# destilador_pcb.net
KiCad netlist of a schematic drawn in EAGLE
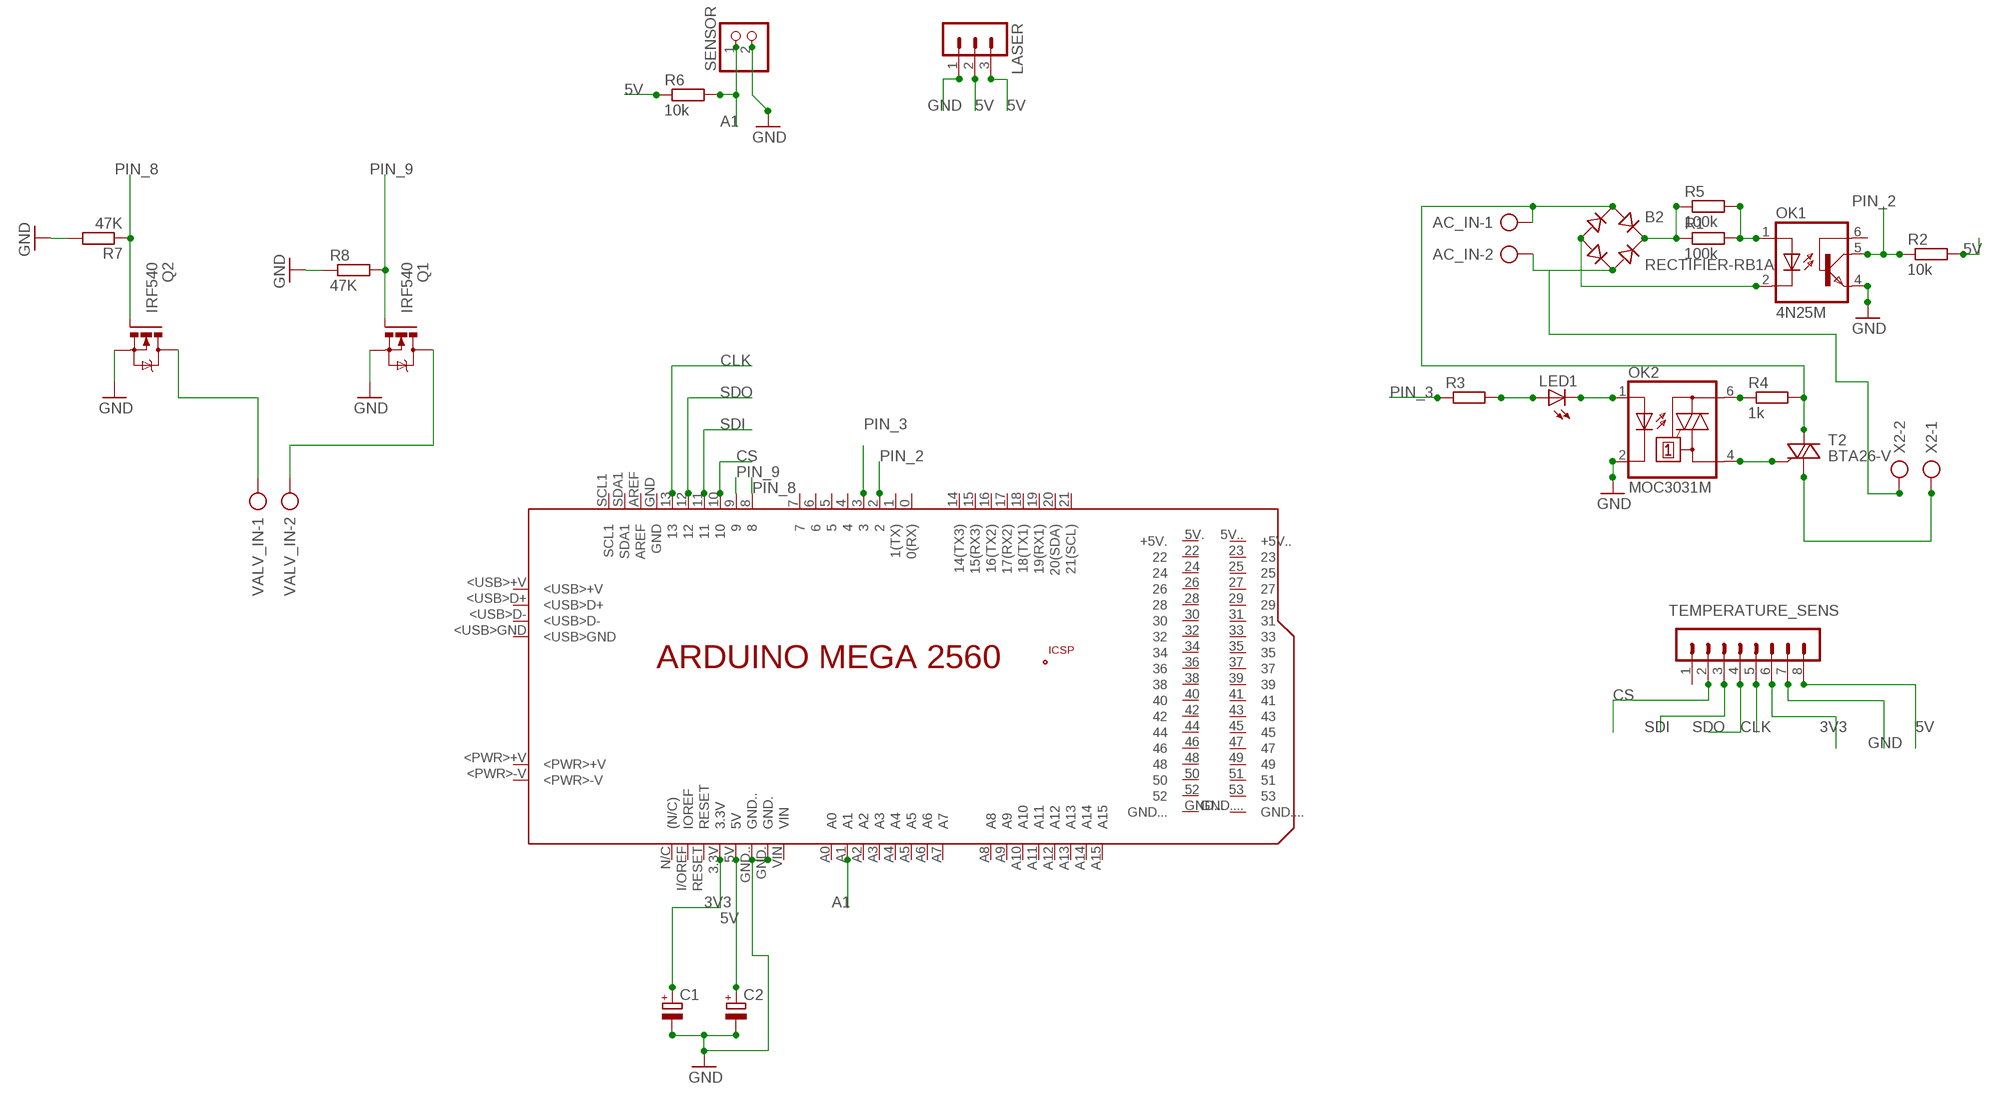
[diagram p0: schematic, sheet 1]

(export (version "E")
  (design (tool "Eeschema 10.0.6"))
  (components
    (comp (ref "AC_IN")
      (value "AK300/2")
      (footprint "eagle-import:AK300_2")
      (libsource (lib "eagle-import") (part "AK300/2"))
    )
    (comp (ref "B2")
      (value "RECTIFIER-RB1A")
      (footprint "eagle-import:RB1A")
      (libsource (lib "eagle-import") (part "RECTIFIER-RB1A"))
    )
    (comp (ref "C1")
      (value "CPOL-EUE2,5-6E")
      (footprint "eagle-import:E2,5-6E")
      (libsource (lib "eagle-import") (part "CPOL-EUE2,5-6E"))
    )
    (comp (ref "C2")
      (value "CPOL-EUE2,5-6E")
      (footprint "eagle-import:E2,5-6E")
      (libsource (lib "eagle-import") (part "CPOL-EUE2,5-6E"))
    )
    (comp (ref "LASER")
      (value "MA03-1")
      (footprint "eagle-import:MA03-1")
      (libsource (lib "eagle-import") (part "MA03-1"))
    )
    (comp (ref "LED1")
      (value "LED5MM")
      (footprint "eagle-import:LED5MM")
      (libsource (lib "eagle-import") (part "LED5MM"))
    )
    (comp (ref "OK1")
      (value "4N25M")
      (footprint "eagle-import:DIL06")
      (fields (field (name "MPN") "4N25-M"))
      (libsource (lib "eagle-import") (part "4N?M25"))
    )
    (comp (ref "OK2")
      (value "MOC3031M")
      (footprint "eagle-import:DIL06")
      (fields (field (name "MF") "FAIRCHILD SEMICONDUCTOR"))
      (libsource (lib "eagle-import") (part "MOC3031M"))
    )
    (comp (ref "PCB1")
      (value "ARDUINO_MEGA2560")
      (footprint "eagle-import:ARDUINO_MEGA2560")
      (libsource (lib "eagle-import") (part "ARDUINO_MEGA2560"))
    )
    (comp (ref "Q1")
      (value "IRF540")
      (footprint "eagle-import:TO220BV")
      (libsource (lib "eagle-import") (part "IRF540"))
    )
    (comp (ref "Q2")
      (value "IRF540")
      (footprint "eagle-import:TO220BV")
      (libsource (lib "eagle-import") (part "IRF540"))
    )
    (comp (ref "R1")
      (value "100k")
      (footprint "eagle-import:0207_7")
      (libsource (lib "eagle-import") (part "R-EU_0207/7"))
    )
    (comp (ref "R2")
      (value "10k")
      (footprint "eagle-import:0207_7")
      (libsource (lib "eagle-import") (part "R-EU_0207/7"))
    )
    (comp (ref "R3")
      (value "R-EU_0207/7")
      (footprint "eagle-import:0207_7")
      (libsource (lib "eagle-import") (part "R-EU_0207/7"))
    )
    (comp (ref "R4")
      (value "1k")
      (footprint "eagle-import:0207_7")
      (libsource (lib "eagle-import") (part "R-EU_0207/7"))
    )
    (comp (ref "R5")
      (value "100k")
      (footprint "eagle-import:0207_7")
      (libsource (lib "eagle-import") (part "R-EU_0207/7"))
    )
    (comp (ref "R6")
      (value "10k")
      (footprint "eagle-import:0207_7")
      (libsource (lib "eagle-import") (part "R-EU_0207/7"))
    )
    (comp (ref "R7")
      (value "47K")
      (footprint "eagle-import:0207_7")
      (libsource (lib "eagle-import") (part "R-EU_0207/7"))
    )
    (comp (ref "R8")
      (value "47K")
      (footprint "eagle-import:0207_7")
      (libsource (lib "eagle-import") (part "R-EU_0207/7"))
    )
    (comp (ref "SENSOR")
      (value "PINHD-1X2")
      (footprint "eagle-import:1X02")
      (libsource (lib "eagle-import") (part "PINHD-1X2"))
    )
    (comp (ref "T2")
      (value "BTA26-V")
      (footprint "eagle-import:TOP3S-1")
      (libsource (lib "eagle-import") (part "BTA26-V"))
    )
    (comp (ref "TEMPERATURE_SENS")
      (value "MA08-1")
      (footprint "eagle-import:MA08-1")
      (libsource (lib "eagle-import") (part "MA08-1"))
    )
    (comp (ref "VALV_IN")
      (value "AK500/2-H")
      (footprint "eagle-import:AK500_2-H")
      (libsource (lib "eagle-import") (part "AK500/2-H"))
    )
    (comp (ref "X2")
      (value "AK300/2")
      (footprint "eagle-import:AK300_2")
      (libsource (lib "eagle-import") (part "AK300/2"))
    )
  )
  (nets
    (net (code "1") (name "/3V3") (class "Default")
      (node (ref "C1") (pin "+") (pinfunction "+_+") (pintype "passive"))
      (node (ref "PCB1") (pin "3.3V") (pinfunction "3.3V_3.3V") (pintype "bidirectional"))
      (node (ref "TEMPERATURE_SENS") (pin "6") (pinfunction "6_6") (pintype "passive"))
    )
    (net (code "2") (name "/5V") (class "Default")
      (node (ref "C2") (pin "+") (pinfunction "+_+") (pintype "passive"))
      (node (ref "LASER") (pin "2") (pinfunction "2_2") (pintype "passive"))
      (node (ref "LASER") (pin "3") (pinfunction "3_3") (pintype "passive"))
      (node (ref "PCB1") (pin "5V") (pinfunction "5V_5V") (pintype "bidirectional"))
      (node (ref "R2") (pin "2") (pinfunction "2_2") (pintype "passive"))
      (node (ref "R6") (pin "1") (pinfunction "1_1") (pintype "passive"))
      (node (ref "TEMPERATURE_SENS") (pin "8") (pinfunction "8_8") (pintype "passive"))
    )
    (net (code "3") (name "/A1") (class "Default")
      (node (ref "PCB1") (pin "A1") (pinfunction "A1_A1") (pintype "bidirectional"))
      (node (ref "R6") (pin "2") (pinfunction "2_2") (pintype "passive"))
      (node (ref "SENSOR") (pin "1") (pinfunction "1_1") (pintype "passive"))
    )
    (net (code "4") (name "/CLK") (class "Default")
      (node (ref "PCB1") (pin "13") (pinfunction "13_13") (pintype "bidirectional"))
      (node (ref "TEMPERATURE_SENS") (pin "5") (pinfunction "5_5") (pintype "passive"))
    )
    (net (code "5") (name "/CS") (class "Default")
      (node (ref "PCB1") (pin "10") (pinfunction "10_10") (pintype "bidirectional"))
      (node (ref "TEMPERATURE_SENS") (pin "2") (pinfunction "2_2") (pintype "passive"))
    )
    (net (code "6") (name "/PIN_2") (class "Default")
      (node (ref "OK1") (pin "5") (pinfunction "COL_5") (pintype "passive"))
      (node (ref "PCB1") (pin "2") (pinfunction "2_2") (pintype "bidirectional"))
      (node (ref "R2") (pin "1") (pinfunction "1_1") (pintype "passive"))
    )
    (net (code "7") (name "/PIN_3") (class "Default")
      (node (ref "PCB1") (pin "3") (pinfunction "3_3") (pintype "bidirectional"))
      (node (ref "R3") (pin "1") (pinfunction "1_1") (pintype "passive"))
    )
    (net (code "8") (name "/PIN_8") (class "Default")
      (node (ref "PCB1") (pin "8") (pinfunction "8_8") (pintype "bidirectional"))
      (node (ref "Q2") (pin "G") (pinfunction "G_G") (pintype "passive"))
      (node (ref "R7") (pin "1") (pinfunction "1_1") (pintype "passive"))
    )
    (net (code "9") (name "/PIN_9") (class "Default")
      (node (ref "PCB1") (pin "9") (pinfunction "9_9") (pintype "bidirectional"))
      (node (ref "Q1") (pin "G") (pinfunction "G_G") (pintype "passive"))
      (node (ref "R8") (pin "2") (pinfunction "2_2") (pintype "passive"))
    )
    (net (code "10") (name "/SDI") (class "Default")
      (node (ref "PCB1") (pin "11") (pinfunction "11_11") (pintype "bidirectional"))
      (node (ref "TEMPERATURE_SENS") (pin "3") (pinfunction "3_3") (pintype "passive"))
    )
    (net (code "11") (name "/SDO") (class "Default")
      (node (ref "PCB1") (pin "12") (pinfunction "12_12") (pintype "bidirectional"))
      (node (ref "TEMPERATURE_SENS") (pin "4") (pinfunction "4_4") (pintype "passive"))
    )
    (net (code "12") (name "GND") (class "Default")
      (node (ref "C1") (pin "-") (pinfunction "-_-") (pintype "passive"))
      (node (ref "C2") (pin "-") (pinfunction "-_-") (pintype "passive"))
      (node (ref "LASER") (pin "1") (pinfunction "1_1") (pintype "passive"))
      (node (ref "OK1") (pin "4") (pinfunction "EMI_4") (pintype "passive"))
      (node (ref "OK2") (pin "2") (pinfunction "C_2") (pintype "passive"))
      (node (ref "PCB1") (pin "GND.") (pinfunction "GND._GND.") (pintype "bidirectional"))
      (node (ref "PCB1") (pin "GND..") (pinfunction "GND.._GND..") (pintype "bidirectional"))
      (node (ref "Q1") (pin "S") (pinfunction "S_S") (pintype "passive"))
      (node (ref "Q2") (pin "S") (pinfunction "S_S") (pintype "passive"))
      (node (ref "R7") (pin "2") (pinfunction "2_2") (pintype "passive"))
      (node (ref "R8") (pin "1") (pinfunction "1_1") (pintype "passive"))
      (node (ref "SENSOR") (pin "2") (pinfunction "2_2") (pintype "passive"))
      (node (ref "TEMPERATURE_SENS") (pin "7") (pinfunction "7_7") (pintype "passive"))
    )
    (net (code "13") (name "Net-(AC_INA-KL)") (class "Default")
      (node (ref "AC_IN") (pin "1") (pinfunction "KL_1") (pintype "passive"))
      (node (ref "B2") (pin "AC1") (pinfunction "AC1_AC1") (pintype "passive"))
      (node (ref "R4") (pin "2") (pinfunction "2_2") (pintype "passive"))
      (node (ref "T2") (pin "A2") (pinfunction "A2_A2") (pintype "passive"))
    )
    (net (code "14") (name "Net-(AC_INB-KL)") (class "Default")
      (node (ref "AC_IN") (pin "2") (pinfunction "KL_2") (pintype "passive"))
      (node (ref "B2") (pin "AC2") (pinfunction "AC2_AC2") (pintype "passive"))
      (node (ref "X2") (pin "2") (pinfunction "KL_2") (pintype "passive"))
    )
    (net (code "15") (name "Net-(B2-Pad+)") (class "Default")
      (node (ref "B2") (pin "+") (pinfunction "+_+") (pintype "passive"))
      (node (ref "R1") (pin "1") (pinfunction "1_1") (pintype "passive"))
      (node (ref "R5") (pin "1") (pinfunction "1_1") (pintype "passive"))
    )
    (net (code "16") (name "Net-(LED1-C)") (class "Default")
      (node (ref "LED1") (pin "K") (pinfunction "C_K") (pintype "passive"))
      (node (ref "OK2") (pin "1") (pinfunction "A_1") (pintype "passive"))
    )
    (net (code "17") (name "Net-(LED1-PadA)") (class "Default")
      (node (ref "LED1") (pin "A") (pinfunction "A_A") (pintype "passive"))
      (node (ref "R3") (pin "2") (pinfunction "2_2") (pintype "passive"))
    )
    (net (code "18") (name "Net-(OK1-A)") (class "Default")
      (node (ref "OK1") (pin "1") (pinfunction "A_1") (pintype "passive"))
      (node (ref "R1") (pin "2") (pinfunction "2_2") (pintype "passive"))
      (node (ref "R5") (pin "2") (pinfunction "2_2") (pintype "passive"))
    )
    (net (code "19") (name "Net-(OK1-C)") (class "Default")
      (node (ref "B2") (pin "-") (pinfunction "-_-") (pintype "passive"))
      (node (ref "OK1") (pin "2") (pinfunction "C_2") (pintype "passive"))
    )
    (net (code "20") (name "Net-(OK2-A1)") (class "Default")
      (node (ref "OK2") (pin "4") (pinfunction "A1_4") (pintype "passive"))
      (node (ref "T2") (pin "G") (pinfunction "G_G") (pintype "passive"))
    )
    (net (code "21") (name "Net-(OK2-A2)") (class "Default")
      (node (ref "OK2") (pin "6") (pinfunction "A2_6") (pintype "passive"))
      (node (ref "R4") (pin "1") (pinfunction "1_1") (pintype "passive"))
    )
    (net (code "22") (name "Net-(VALV_INA-KL)") (class "Default")
      (node (ref "Q2") (pin "D") (pinfunction "D_D") (pintype "passive"))
      (node (ref "VALV_IN") (pin "1") (pinfunction "KL_1") (pintype "passive"))
    )
    (net (code "23") (name "Net-(VALV_INB-KL)") (class "Default")
      (node (ref "Q1") (pin "D") (pinfunction "D_D") (pintype "passive"))
      (node (ref "VALV_IN") (pin "2") (pinfunction "KL_2") (pintype "passive"))
    )
    (net (code "24") (name "Net-(X2A-KL)") (class "Default")
      (node (ref "T2") (pin "A1") (pinfunction "A1_A1") (pintype "passive"))
      (node (ref "X2") (pin "1") (pinfunction "KL_1") (pintype "passive"))
    )
    (net (code "25") (name "unconnected-(OK1-BAS-Pad6)") (class "Default")
      (node (ref "OK1") (pin "6") (pinfunction "BAS_6") (pintype "passive"))
    )
    (net (code "26") (name "unconnected-(PCB1-(N{slash}C)-PadN{slash}C)") (class "Default")
      (node (ref "PCB1") (pin "N/C") (pinfunction "(N/C)_N/C") (pintype "bidirectional"))
    )
    (net (code "27") (name "unconnected-(PCB1-+5V.-Pad5V.)") (class "Default")
      (node (ref "PCB1") (pin "5V.") (pinfunction "+5V._5V.") (pintype "bidirectional"))
    )
    (net (code "28") (name "unconnected-(PCB1-+5V..-Pad5V..)") (class "Default")
      (node (ref "PCB1") (pin "5V..") (pinfunction "+5V.._5V..") (pintype "bidirectional"))
    )
    (net (code "29") (name "unconnected-(PCB1-0(RX)-Pad0)") (class "Default")
      (node (ref "PCB1") (pin "0") (pinfunction "0(RX)_0") (pintype "bidirectional"))
    )
    (net (code "30") (name "unconnected-(PCB1-1(TX)-Pad1)") (class "Default")
      (node (ref "PCB1") (pin "1") (pinfunction "1(TX)_1") (pintype "bidirectional"))
    )
    (net (code "31") (name "unconnected-(PCB1-14(TX3)-Pad14)") (class "Default")
      (node (ref "PCB1") (pin "14") (pinfunction "14(TX3)_14") (pintype "bidirectional"))
    )
    (net (code "32") (name "unconnected-(PCB1-15(RX3)-Pad15)") (class "Default")
      (node (ref "PCB1") (pin "15") (pinfunction "15(RX3)_15") (pintype "bidirectional"))
    )
    (net (code "33") (name "unconnected-(PCB1-16(TX2)-Pad16)") (class "Default")
      (node (ref "PCB1") (pin "16") (pinfunction "16(TX2)_16") (pintype "bidirectional"))
    )
    (net (code "34") (name "unconnected-(PCB1-17(RX2)-Pad17)") (class "Default")
      (node (ref "PCB1") (pin "17") (pinfunction "17(RX2)_17") (pintype "bidirectional"))
    )
    (net (code "35") (name "unconnected-(PCB1-18(TX1)-Pad18)") (class "Default")
      (node (ref "PCB1") (pin "18") (pinfunction "18(TX1)_18") (pintype "bidirectional"))
    )
    (net (code "36") (name "unconnected-(PCB1-19(RX1)-Pad19)") (class "Default")
      (node (ref "PCB1") (pin "19") (pinfunction "19(RX1)_19") (pintype "bidirectional"))
    )
    (net (code "37") (name "unconnected-(PCB1-20(SDA)-Pad20)") (class "Default")
      (node (ref "PCB1") (pin "20") (pinfunction "20(SDA)_20") (pintype "bidirectional"))
    )
    (net (code "38") (name "unconnected-(PCB1-21(SCL)-Pad21)") (class "Default")
      (node (ref "PCB1") (pin "21") (pinfunction "21(SCL)_21") (pintype "bidirectional"))
    )
    (net (code "39") (name "unconnected-(PCB1-IOREF-PadI{slash}OREF)") (class "Default")
      (node (ref "PCB1") (pin "I/OREF") (pinfunction "IOREF_I/OREF") (pintype "bidirectional"))
    )
    (net (code "40") (name "unconnected-(PCB1-Pad+5V_)") (class "Default")
      (node (ref "PCB1") (pin "+5V_") (pinfunction "+5V__+5V_") (pintype "bidirectional"))
    )
    (net (code "41") (name "unconnected-(PCB1-Pad4)") (class "Default")
      (node (ref "PCB1") (pin "4") (pinfunction "4_4") (pintype "bidirectional"))
    )
    (net (code "42") (name "unconnected-(PCB1-Pad5)") (class "Default")
      (node (ref "PCB1") (pin "5") (pinfunction "5_5") (pintype "bidirectional"))
    )
    (net (code "43") (name "unconnected-(PCB1-Pad6)") (class "Default")
      (node (ref "PCB1") (pin "6") (pinfunction "6_6") (pintype "bidirectional"))
    )
    (net (code "44") (name "unconnected-(PCB1-Pad7)") (class "Default")
      (node (ref "PCB1") (pin "7") (pinfunction "7_7") (pintype "bidirectional"))
    )
    (net (code "45") (name "unconnected-(PCB1-Pad22)") (class "Default")
      (node (ref "PCB1") (pin "22") (pinfunction "22_22") (pintype "bidirectional"))
    )
    (net (code "46") (name "unconnected-(PCB1-Pad23)") (class "Default")
      (node (ref "PCB1") (pin "23") (pinfunction "23_23") (pintype "bidirectional"))
    )
    (net (code "47") (name "unconnected-(PCB1-Pad24)") (class "Default")
      (node (ref "PCB1") (pin "24") (pinfunction "24_24") (pintype "bidirectional"))
    )
    (net (code "48") (name "unconnected-(PCB1-Pad25)") (class "Default")
      (node (ref "PCB1") (pin "25") (pinfunction "25_25") (pintype "bidirectional"))
    )
    (net (code "49") (name "unconnected-(PCB1-Pad26)") (class "Default")
      (node (ref "PCB1") (pin "26") (pinfunction "26_26") (pintype "bidirectional"))
    )
    (net (code "50") (name "unconnected-(PCB1-Pad27)") (class "Default")
      (node (ref "PCB1") (pin "27") (pinfunction "27_27") (pintype "bidirectional"))
    )
    (net (code "51") (name "unconnected-(PCB1-Pad28)") (class "Default")
      (node (ref "PCB1") (pin "28") (pinfunction "28_28") (pintype "bidirectional"))
    )
    (net (code "52") (name "unconnected-(PCB1-Pad29)") (class "Default")
      (node (ref "PCB1") (pin "29") (pinfunction "29_29") (pintype "bidirectional"))
    )
    (net (code "53") (name "unconnected-(PCB1-Pad30)") (class "Default")
      (node (ref "PCB1") (pin "30") (pinfunction "30_30") (pintype "bidirectional"))
    )
    (net (code "54") (name "unconnected-(PCB1-Pad31)") (class "Default")
      (node (ref "PCB1") (pin "31") (pinfunction "31_31") (pintype "bidirectional"))
    )
    (net (code "55") (name "unconnected-(PCB1-Pad32)") (class "Default")
      (node (ref "PCB1") (pin "32") (pinfunction "32_32") (pintype "bidirectional"))
    )
    (net (code "56") (name "unconnected-(PCB1-Pad33)") (class "Default")
      (node (ref "PCB1") (pin "33") (pinfunction "33_33") (pintype "bidirectional"))
    )
    (net (code "57") (name "unconnected-(PCB1-Pad34)") (class "Default")
      (node (ref "PCB1") (pin "34") (pinfunction "34_34") (pintype "bidirectional"))
    )
    (net (code "58") (name "unconnected-(PCB1-Pad35)") (class "Default")
      (node (ref "PCB1") (pin "35") (pinfunction "35_35") (pintype "bidirectional"))
    )
    (net (code "59") (name "unconnected-(PCB1-Pad36)") (class "Default")
      (node (ref "PCB1") (pin "36") (pinfunction "36_36") (pintype "bidirectional"))
    )
    (net (code "60") (name "unconnected-(PCB1-Pad37)") (class "Default")
      (node (ref "PCB1") (pin "37") (pinfunction "37_37") (pintype "bidirectional"))
    )
    (net (code "61") (name "unconnected-(PCB1-Pad38)") (class "Default")
      (node (ref "PCB1") (pin "38") (pinfunction "38_38") (pintype "bidirectional"))
    )
    (net (code "62") (name "unconnected-(PCB1-Pad39)") (class "Default")
      (node (ref "PCB1") (pin "39") (pinfunction "39_39") (pintype "bidirectional"))
    )
    (net (code "63") (name "unconnected-(PCB1-Pad40)") (class "Default")
      (node (ref "PCB1") (pin "40") (pinfunction "40_40") (pintype "bidirectional"))
    )
    (net (code "64") (name "unconnected-(PCB1-Pad41)") (class "Default")
      (node (ref "PCB1") (pin "41") (pinfunction "41_41") (pintype "bidirectional"))
    )
    (net (code "65") (name "unconnected-(PCB1-Pad42)") (class "Default")
      (node (ref "PCB1") (pin "42") (pinfunction "42_42") (pintype "bidirectional"))
    )
    (net (code "66") (name "unconnected-(PCB1-Pad43)") (class "Default")
      (node (ref "PCB1") (pin "43") (pinfunction "43_43") (pintype "bidirectional"))
    )
    (net (code "67") (name "unconnected-(PCB1-Pad44)") (class "Default")
      (node (ref "PCB1") (pin "44") (pinfunction "44_44") (pintype "bidirectional"))
    )
    (net (code "68") (name "unconnected-(PCB1-Pad45)") (class "Default")
      (node (ref "PCB1") (pin "45") (pinfunction "45_45") (pintype "bidirectional"))
    )
    (net (code "69") (name "unconnected-(PCB1-Pad46)") (class "Default")
      (node (ref "PCB1") (pin "46") (pinfunction "46_46") (pintype "bidirectional"))
    )
    (net (code "70") (name "unconnected-(PCB1-Pad47)") (class "Default")
      (node (ref "PCB1") (pin "47") (pinfunction "47_47") (pintype "bidirectional"))
    )
    (net (code "71") (name "unconnected-(PCB1-Pad48)") (class "Default")
      (node (ref "PCB1") (pin "48") (pinfunction "48_48") (pintype "bidirectional"))
    )
    (net (code "72") (name "unconnected-(PCB1-Pad49)") (class "Default")
      (node (ref "PCB1") (pin "49") (pinfunction "49_49") (pintype "bidirectional"))
    )
    (net (code "73") (name "unconnected-(PCB1-Pad50)") (class "Default")
      (node (ref "PCB1") (pin "50") (pinfunction "50_50") (pintype "bidirectional"))
    )
    (net (code "74") (name "unconnected-(PCB1-Pad51)") (class "Default")
      (node (ref "PCB1") (pin "51") (pinfunction "51_51") (pintype "bidirectional"))
    )
    (net (code "75") (name "unconnected-(PCB1-Pad52)") (class "Default")
      (node (ref "PCB1") (pin "52") (pinfunction "52_52") (pintype "bidirectional"))
    )
    (net (code "76") (name "unconnected-(PCB1-Pad53)") (class "Default")
      (node (ref "PCB1") (pin "53") (pinfunction "53_53") (pintype "bidirectional"))
    )
    (net (code "77") (name "unconnected-(PCB1-Pad<PWR>+V)") (class "Default")
      (node (ref "PCB1") (pin "<PWR>+V") (pinfunction "<PWR>+V_<PWR>+V") (pintype "no_connect"))
    )
    (net (code "78") (name "unconnected-(PCB1-Pad<PWR>-V)") (class "Default")
      (node (ref "PCB1") (pin "<PWR>-V") (pinfunction "<PWR>-V_<PWR>-V") (pintype "no_connect"))
    )
    (net (code "79") (name "unconnected-(PCB1-Pad<USB>+V)") (class "Default")
      (node (ref "PCB1") (pin "<USB>+V") (pinfunction "<USB>+V_<USB>+V") (pintype "no_connect"))
    )
    (net (code "80") (name "unconnected-(PCB1-Pad<USB>D+)") (class "Default")
      (node (ref "PCB1") (pin "<USB>D+") (pinfunction "<USB>D+_<USB>D+") (pintype "no_connect"))
    )
    (net (code "81") (name "unconnected-(PCB1-Pad<USB>D-)") (class "Default")
      (node (ref "PCB1") (pin "<USB>D-") (pinfunction "<USB>D-_<USB>D-") (pintype "no_connect"))
    )
    (net (code "82") (name "unconnected-(PCB1-Pad<USB>GND)") (class "Default")
      (node (ref "PCB1") (pin "<USB>GND") (pinfunction "<USB>GND_<USB>GND") (pintype "no_connect"))
    )
    (net (code "83") (name "unconnected-(PCB1-PadA0)") (class "Default")
      (node (ref "PCB1") (pin "A0") (pinfunction "A0_A0") (pintype "bidirectional"))
    )
    (net (code "84") (name "unconnected-(PCB1-PadA2)") (class "Default")
      (node (ref "PCB1") (pin "A2") (pinfunction "A2_A2") (pintype "bidirectional"))
    )
    (net (code "85") (name "unconnected-(PCB1-PadA3)") (class "Default")
      (node (ref "PCB1") (pin "A3") (pinfunction "A3_A3") (pintype "bidirectional"))
    )
    (net (code "86") (name "unconnected-(PCB1-PadA4)") (class "Default")
      (node (ref "PCB1") (pin "A4") (pinfunction "A4_A4") (pintype "bidirectional"))
    )
    (net (code "87") (name "unconnected-(PCB1-PadA5)") (class "Default")
      (node (ref "PCB1") (pin "A5") (pinfunction "A5_A5") (pintype "bidirectional"))
    )
    (net (code "88") (name "unconnected-(PCB1-PadA6)") (class "Default")
      (node (ref "PCB1") (pin "A6") (pinfunction "A6_A6") (pintype "bidirectional"))
    )
    (net (code "89") (name "unconnected-(PCB1-PadA7)") (class "Default")
      (node (ref "PCB1") (pin "A7") (pinfunction "A7_A7") (pintype "bidirectional"))
    )
    (net (code "90") (name "unconnected-(PCB1-PadA8)") (class "Default")
      (node (ref "PCB1") (pin "A8") (pinfunction "A8_A8") (pintype "bidirectional"))
    )
    (net (code "91") (name "unconnected-(PCB1-PadA9)") (class "Default")
      (node (ref "PCB1") (pin "A9") (pinfunction "A9_A9") (pintype "bidirectional"))
    )
    (net (code "92") (name "unconnected-(PCB1-PadA10)") (class "Default")
      (node (ref "PCB1") (pin "A10") (pinfunction "A10_A10") (pintype "bidirectional"))
    )
    (net (code "93") (name "unconnected-(PCB1-PadA11)") (class "Default")
      (node (ref "PCB1") (pin "A11") (pinfunction "A11_A11") (pintype "bidirectional"))
    )
    (net (code "94") (name "unconnected-(PCB1-PadA12)") (class "Default")
      (node (ref "PCB1") (pin "A12") (pinfunction "A12_A12") (pintype "bidirectional"))
    )
    (net (code "95") (name "unconnected-(PCB1-PadA13)") (class "Default")
      (node (ref "PCB1") (pin "A13") (pinfunction "A13_A13") (pintype "bidirectional"))
    )
    (net (code "96") (name "unconnected-(PCB1-PadA14)") (class "Default")
      (node (ref "PCB1") (pin "A14") (pinfunction "A14_A14") (pintype "bidirectional"))
    )
    (net (code "97") (name "unconnected-(PCB1-PadA15)") (class "Default")
      (node (ref "PCB1") (pin "A15") (pinfunction "A15_A15") (pintype "bidirectional"))
    )
    (net (code "98") (name "unconnected-(PCB1-PadAREF)") (class "Default")
      (node (ref "PCB1") (pin "AREF") (pinfunction "AREF_AREF") (pintype "bidirectional"))
    )
    (net (code "99") (name "unconnected-(PCB1-PadGND)") (class "Default")
      (node (ref "PCB1") (pin "GND") (pinfunction "GND_GND") (pintype "bidirectional"))
    )
    (net (code "100") (name "unconnected-(PCB1-PadGND...)") (class "Default")
      (node (ref "PCB1") (pin "GND...") (pinfunction "GND..._GND...") (pintype "bidirectional"))
    )
    (net (code "101") (name "unconnected-(PCB1-PadGND....)") (class "Default")
      (node (ref "PCB1") (pin "GND....") (pinfunction "GND...._GND....") (pintype "bidirectional"))
    )
    (net (code "102") (name "unconnected-(PCB1-PadGND__)") (class "Default")
      (node (ref "PCB1") (pin "GND__") (pinfunction "GND___GND__") (pintype "bidirectional"))
    )
    (net (code "103") (name "unconnected-(PCB1-PadMISO)") (class "Default")
      (node (ref "PCB1") (pin "MISO") (pinfunction "MISO_MISO") (pintype "bidirectional"))
    )
    (net (code "104") (name "unconnected-(PCB1-PadMOSI)") (class "Default")
      (node (ref "PCB1") (pin "MOSI") (pinfunction "MOSI_MOSI") (pintype "bidirectional"))
    )
    (net (code "105") (name "unconnected-(PCB1-PadRESET)") (class "Default")
      (node (ref "PCB1") (pin "RESET") (pinfunction "RESET_RESET") (pintype "bidirectional"))
    )
    (net (code "106") (name "unconnected-(PCB1-PadRESET.)") (class "Default")
      (node (ref "PCB1") (pin "RESET.") (pinfunction "RESET._RESET.") (pintype "bidirectional"))
    )
    (net (code "107") (name "unconnected-(PCB1-PadSCK)") (class "Default")
      (node (ref "PCB1") (pin "SCK") (pinfunction "SCK_SCK") (pintype "bidirectional"))
    )
    (net (code "108") (name "unconnected-(PCB1-PadSCL1)") (class "Default")
      (node (ref "PCB1") (pin "SCL1") (pinfunction "SCL1_SCL1") (pintype "bidirectional"))
    )
    (net (code "109") (name "unconnected-(PCB1-PadSDA1)") (class "Default")
      (node (ref "PCB1") (pin "SDA1") (pinfunction "SDA1_SDA1") (pintype "bidirectional"))
    )
    (net (code "110") (name "unconnected-(PCB1-PadVIN)") (class "Default")
      (node (ref "PCB1") (pin "VIN") (pinfunction "VIN_VIN") (pintype "bidirectional"))
    )
    (net (code "111") (name "unconnected-(TEMPERATURE_SENS-Pad1)") (class "Default")
      (node (ref "TEMPERATURE_SENS") (pin "1") (pinfunction "1_1") (pintype "passive"))
    )
  )
)
